# SmartLightsMini.net
KiCad netlist of a schematic drawn in EasyEDA
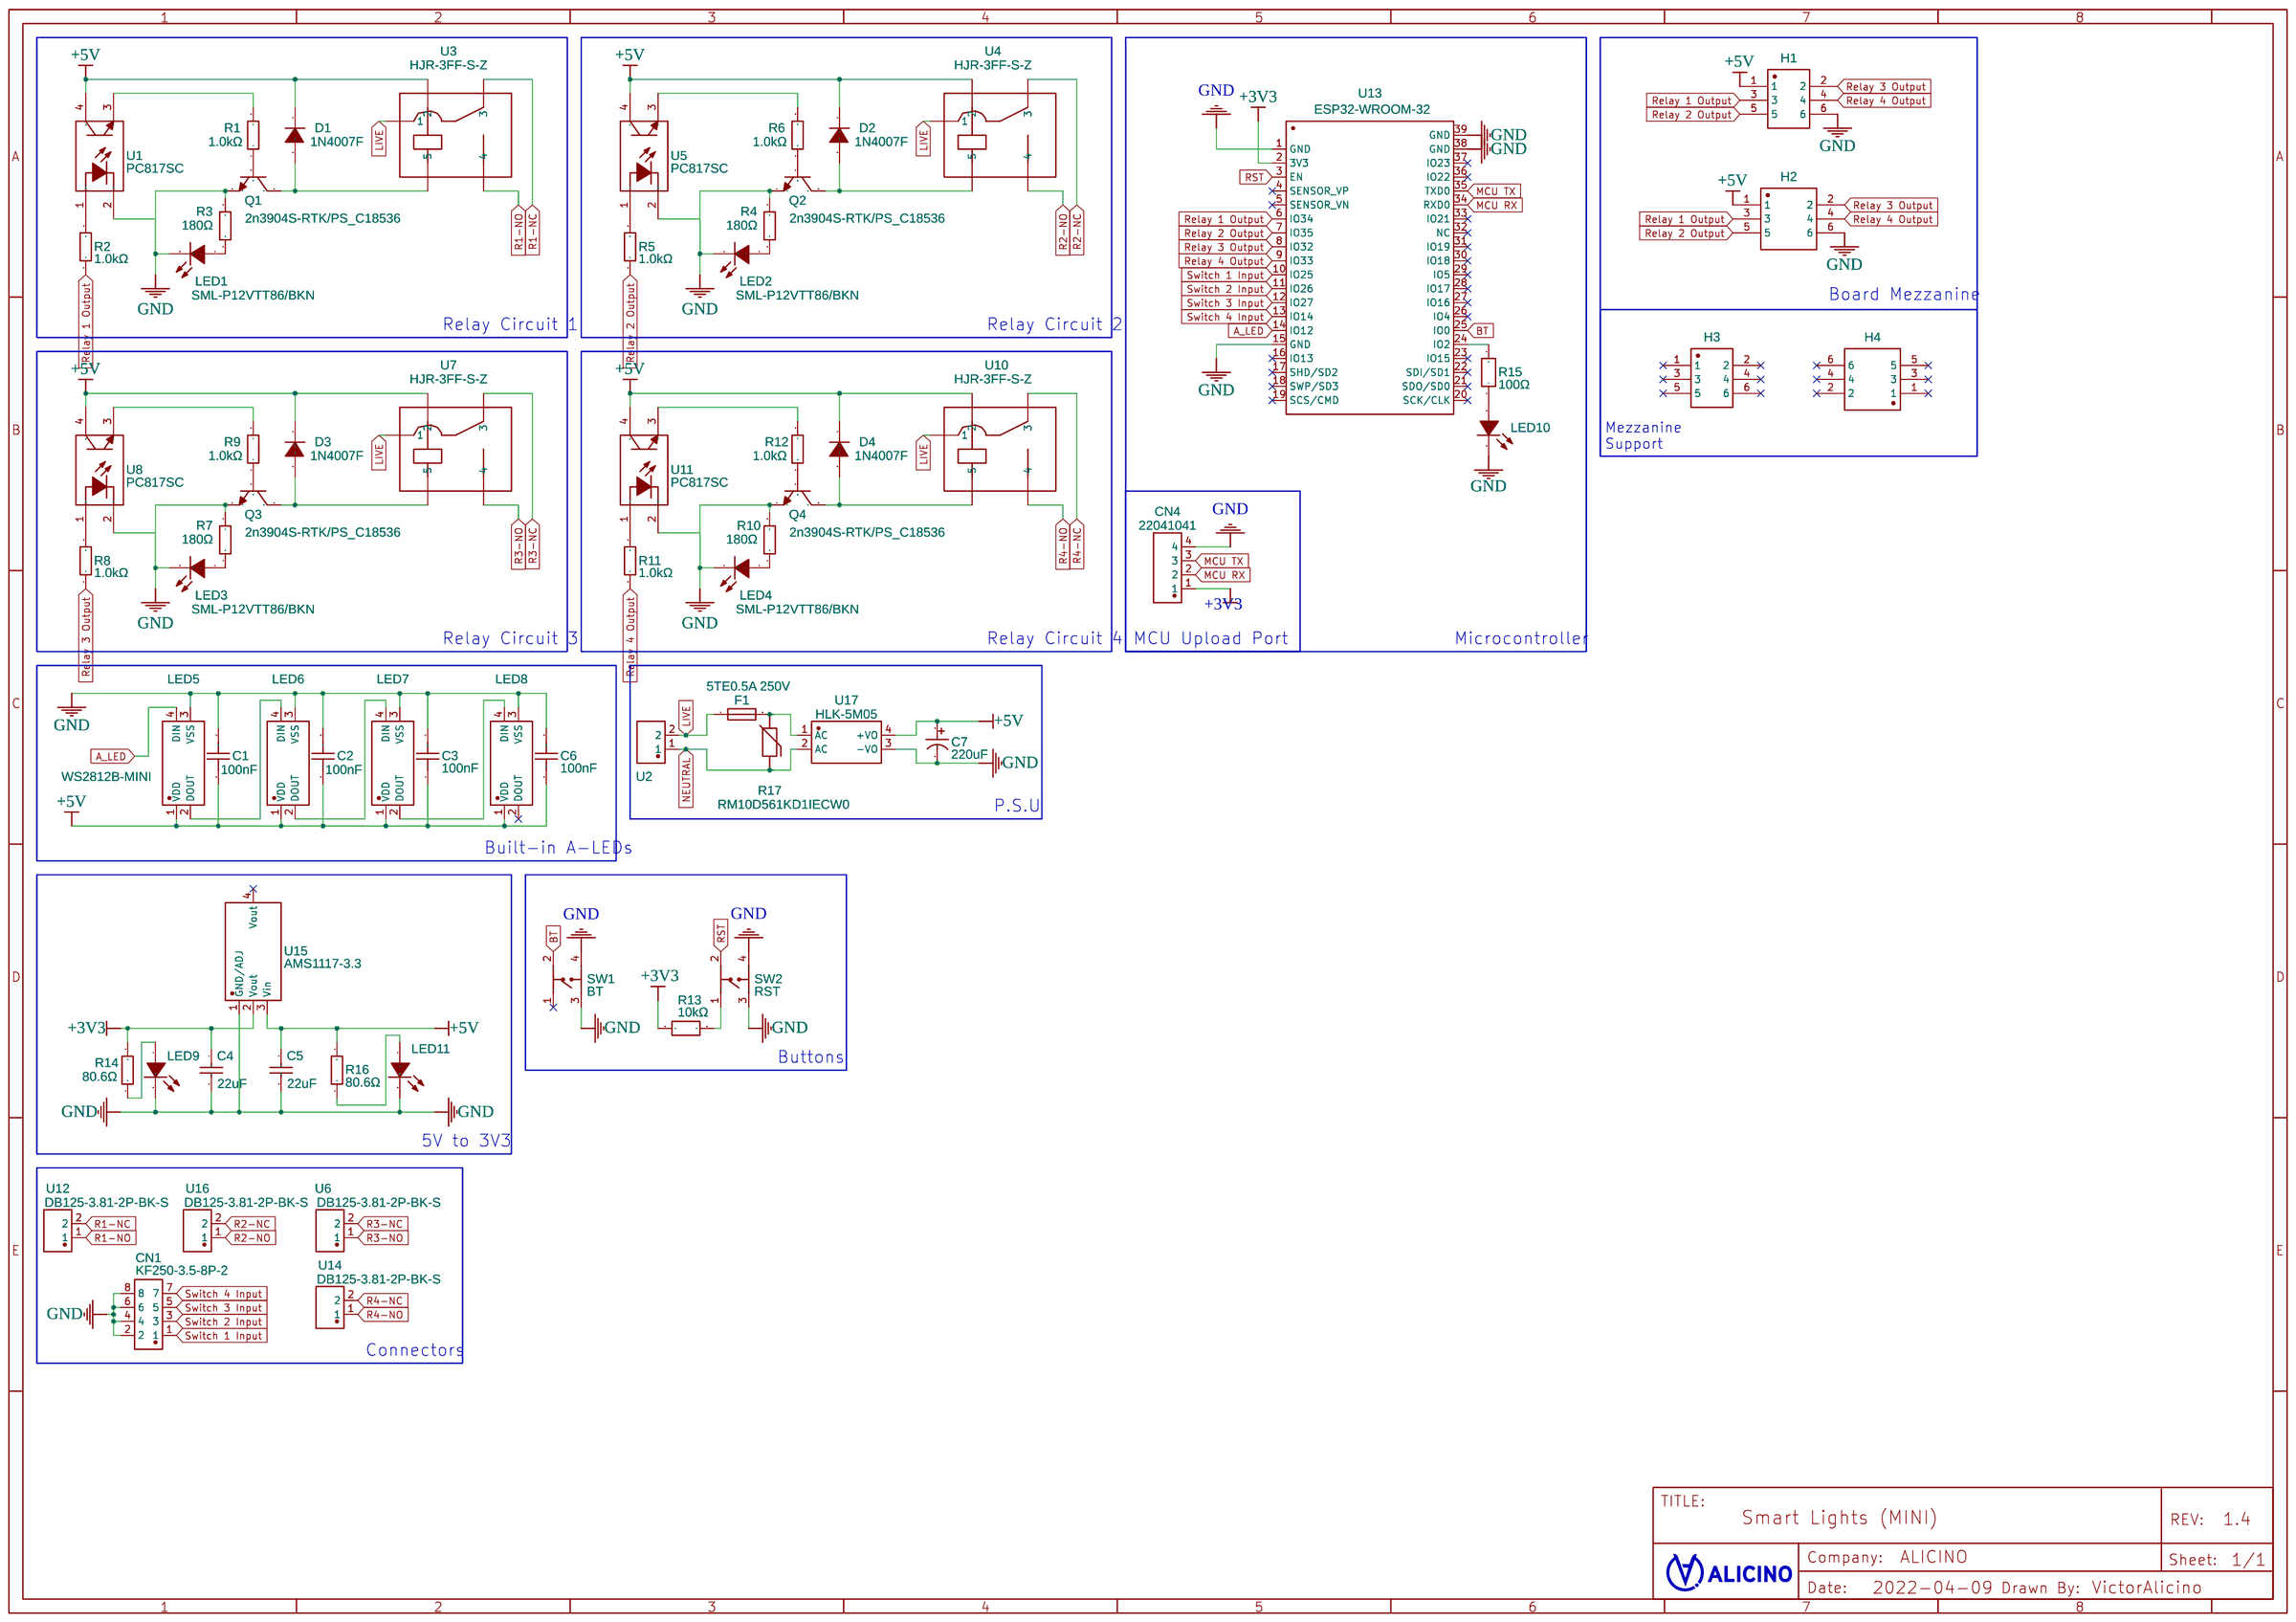
[diagram p0: schematic sheet]

(export (version "E")
  (design (tool "Eeschema 10.0.6"))
  (components
    (comp (ref "C1")
      (value "100nF")
      (fields
        (field (name "BOM_Manufacturer Part") "06035C104KAZ2A")
        (field (name "BOM_Supplier Part") "C212614")
      )
      (libsource (lib "") (part "06035C104KAZ2A"))
    )
    (comp (ref "C2")
      (value "100nF")
      (fields
        (field (name "BOM_Manufacturer Part") "06035C104KAZ2A")
        (field (name "BOM_Supplier Part") "C212614")
      )
      (libsource (lib "") (part "06035C104KAZ2A"))
    )
    (comp (ref "C3")
      (value "100nF")
      (fields
        (field (name "BOM_Manufacturer Part") "06035C104KAZ2A")
        (field (name "BOM_Supplier Part") "C212614")
      )
      (libsource (lib "") (part "06035C104KAZ2A"))
    )
    (comp (ref "C4")
      (value "22uF")
      (fields
        (field (name "BOM_Manufacturer Part") "06036D226MAT2A")
        (field (name "BOM_Supplier Part") "C140720")
      )
      (libsource (lib "") (part "06036D226MAT2A_1"))
    )
    (comp (ref "C5")
      (value "22uF")
      (fields
        (field (name "BOM_Manufacturer Part") "06036D226MAT2A")
        (field (name "BOM_Supplier Part") "C140720")
      )
      (libsource (lib "") (part "06036D226MAT2A"))
    )
    (comp (ref "C6")
      (value "100nF")
      (fields
        (field (name "BOM_Manufacturer Part") "06035C104KAZ2A")
        (field (name "BOM_Supplier Part") "C212614")
      )
      (libsource (lib "") (part "06035C104KAZ2A"))
    )
    (comp (ref "C7")
      (value "220uF")
      (fields
        (field (name "BOM_Manufacturer Part") "EEEHA1C221AP")
        (field (name "BOM_Supplier Part") "C336793")
      )
      (libsource (lib "") (part "EEEHA1C221AP"))
    )
    (comp (ref "CN1")
      (value "KF250-3.5-8P-2")
      (fields (field (name "BOM_Supplier Part") "C475169"))
      (libsource (lib "") (part "KF250-3.5-8P-2"))
    )
    (comp (ref "CN4")
      (value "22041041")
      (fields (field (name "BOM_Supplier Part") "C185196"))
      (libsource (lib "") (part "22041041"))
    )
    (comp (ref "D1")
      (value "1N4007F")
      (fields (field (name "BOM_Supplier Part") "C110856"))
      (libsource (lib "") (part "1N4007F"))
    )
    (comp (ref "D2")
      (value "1N4007F")
      (fields (field (name "BOM_Supplier Part") "C110856"))
      (libsource (lib "") (part "1N4007F"))
    )
    (comp (ref "D3")
      (value "1N4007F")
      (fields (field (name "BOM_Supplier Part") "C110856"))
      (libsource (lib "") (part "1N4007F"))
    )
    (comp (ref "D4")
      (value "1N4007F")
      (fields (field (name "BOM_Supplier Part") "C110856"))
      (libsource (lib "") (part "1N4007F"))
    )
    (comp (ref "F1")
      (value "5TE0.5A 250V")
      (fields (field (name "BOM_Supplier Part") "C140483"))
      (libsource (lib "") (part "5TE0.5A 250V"))
    )
    (comp (ref "H1")
      (value "210SMT-2*3P Gold-plated black")
      (fields (field (name "BOM_Supplier Part") "C124390"))
      (libsource (lib "") (part "210SMT-2*3P Gold-plated black"))
    )
    (comp (ref "H2")
      (value "220S-2*3P H=8.5MM Ytype Gold-plated")
      (fields (field (name "BOM_Supplier Part") "C124421"))
      (libsource (lib "") (part "220S-2*3P H=8.5MM Ytype Gold-plated"))
    )
    (comp (ref "H3")
      (value "210SMT-2*3P Gold-plated black")
      (fields (field (name "BOM_Supplier Part") "C124390"))
      (libsource (lib "") (part "210SMT-2*3P Gold-plated black"))
    )
    (comp (ref "H4")
      (value "220S-2*3P H=8.5MM Ytype Gold-plated")
      (fields (field (name "BOM_Supplier Part") "C124421"))
      (libsource (lib "") (part "220S-2*3P H=8.5MM Ytype Gold-plated_1"))
    )
    (comp (ref "LED1")
      (value "SML-P12VTT86/BKN")
      (fields (field (name "BOM_Supplier Part") "C184649"))
      (libsource (lib "") (part "SML-P12VTT86/BKN"))
    )
    (comp (ref "LED2")
      (value "SML-P12VTT86/BKN")
      (fields (field (name "BOM_Supplier Part") "C184649"))
      (libsource (lib "") (part "SML-P12VTT86/BKN"))
    )
    (comp (ref "LED3")
      (value "SML-P12VTT86/BKN")
      (fields (field (name "BOM_Supplier Part") "C184649"))
      (libsource (lib "") (part "SML-P12VTT86/BKN"))
    )
    (comp (ref "LED4")
      (value "SML-P12VTT86/BKN")
      (fields (field (name "BOM_Supplier Part") "C184649"))
      (libsource (lib "") (part "SML-P12VTT86/BKN"))
    )
    (comp (ref "LED5")
      (value "WS2812B-MINI")
      (fields
        (field (name "BOM_Manufacturer Part") "WS2812B-Mini")
        (field (name "BOM_Supplier Part") "C527089")
      )
      (libsource (lib "") (part "WS2812B-MINI"))
    )
    (comp (ref "LED6")
      (value "WS2812B-MINI")
      (fields
        (field (name "BOM_Manufacturer Part") "WS2812B-Mini")
        (field (name "BOM_Supplier Part") "C527089")
      )
      (libsource (lib "") (part "WS2812B-MINI"))
    )
    (comp (ref "LED7")
      (value "WS2812B-MINI")
      (fields
        (field (name "BOM_Manufacturer Part") "WS2812B-Mini")
        (field (name "BOM_Supplier Part") "C527089")
      )
      (libsource (lib "") (part "WS2812B-MINI"))
    )
    (comp (ref "LED8")
      (value "WS2812B-MINI")
      (fields
        (field (name "BOM_Manufacturer Part") "WS2812B-Mini")
        (field (name "BOM_Supplier Part") "C527089")
      )
      (libsource (lib "") (part "WS2812B-MINI"))
    )
    (comp (ref "LED9")
      (value "SML-P12VTT86/BKN")
      (fields (field (name "BOM_Supplier Part") "C184649"))
      (libsource (lib "") (part "SML-P12VTT86/BKN_1"))
    )
    (comp (ref "LED10")
      (value "19-21UYC/S530-A2/TR8")
      (fields (field (name "BOM_Supplier Part") "C90109"))
      (libsource (lib "") (part "19-21UYC/S530-A2/TR8"))
    )
    (comp (ref "LED11")
      (value "SML-P12VTT86/BKN")
      (fields (field (name "BOM_Supplier Part") "C184649"))
      (libsource (lib "") (part "SML-P12VTT86/BKN_1"))
    )
    (comp (ref "Q1")
      (value "2n3904S-RTK/PS_C18536")
      (fields
        (field (name "BOM_Manufacturer Part") "2n3904S-RTK/PS")
        (field (name "BOM_Supplier Part") "C18536")
      )
      (libsource (lib "") (part "2n3904S-RTK/PS_C18536"))
    )
    (comp (ref "Q2")
      (value "2n3904S-RTK/PS_C18536")
      (fields
        (field (name "BOM_Manufacturer Part") "2n3904S-RTK/PS")
        (field (name "BOM_Supplier Part") "C18536")
      )
      (libsource (lib "") (part "2n3904S-RTK/PS_C18536"))
    )
    (comp (ref "Q3")
      (value "2n3904S-RTK/PS_C18536")
      (fields
        (field (name "BOM_Manufacturer Part") "2n3904S-RTK/PS")
        (field (name "BOM_Supplier Part") "C18536")
      )
      (libsource (lib "") (part "2n3904S-RTK/PS_C18536"))
    )
    (comp (ref "Q4")
      (value "2n3904S-RTK/PS_C18536")
      (fields
        (field (name "BOM_Manufacturer Part") "2n3904S-RTK/PS")
        (field (name "BOM_Supplier Part") "C18536")
      )
      (libsource (lib "") (part "2n3904S-RTK/PS_C18536"))
    )
    (comp (ref "R1")
      (value "1.0kΩ")
      (fields
        (field (name "BOM_Manufacturer Part") "AECR0603F1K00K9")
        (field (name "BOM_Supplier Part") "C328340")
      )
      (libsource (lib "") (part "AECR0603F1K00K9"))
    )
    (comp (ref "R2")
      (value "1.0kΩ")
      (fields
        (field (name "BOM_Manufacturer Part") "AECR0603F1K00K9")
        (field (name "BOM_Supplier Part") "C328340")
      )
      (libsource (lib "") (part "AECR0603F1K00K9"))
    )
    (comp (ref "R3")
      (value "180Ω")
      (fields
        (field (name "BOM_Manufacturer Part") "AECR0603F180RK9")
        (field (name "BOM_Supplier Part") "C352360")
      )
      (libsource (lib "") (part "AECR0603F180RK9"))
    )
    (comp (ref "R4")
      (value "180Ω")
      (fields
        (field (name "BOM_Manufacturer Part") "AECR0603F180RK9")
        (field (name "BOM_Supplier Part") "C352360")
      )
      (libsource (lib "") (part "AECR0603F180RK9"))
    )
    (comp (ref "R5")
      (value "1.0kΩ")
      (fields
        (field (name "BOM_Manufacturer Part") "AECR0603F1K00K9")
        (field (name "BOM_Supplier Part") "C328340")
      )
      (libsource (lib "") (part "AECR0603F1K00K9"))
    )
    (comp (ref "R6")
      (value "1.0kΩ")
      (fields
        (field (name "BOM_Manufacturer Part") "AECR0603F1K00K9")
        (field (name "BOM_Supplier Part") "C328340")
      )
      (libsource (lib "") (part "AECR0603F1K00K9"))
    )
    (comp (ref "R7")
      (value "180Ω")
      (fields
        (field (name "BOM_Manufacturer Part") "AECR0603F180RK9")
        (field (name "BOM_Supplier Part") "C352360")
      )
      (libsource (lib "") (part "AECR0603F180RK9"))
    )
    (comp (ref "R8")
      (value "1.0kΩ")
      (fields
        (field (name "BOM_Manufacturer Part") "AECR0603F1K00K9")
        (field (name "BOM_Supplier Part") "C328340")
      )
      (libsource (lib "") (part "AECR0603F1K00K9"))
    )
    (comp (ref "R9")
      (value "1.0kΩ")
      (fields
        (field (name "BOM_Manufacturer Part") "AECR0603F1K00K9")
        (field (name "BOM_Supplier Part") "C328340")
      )
      (libsource (lib "") (part "AECR0603F1K00K9"))
    )
    (comp (ref "R10")
      (value "180Ω")
      (fields
        (field (name "BOM_Manufacturer Part") "AECR0603F180RK9")
        (field (name "BOM_Supplier Part") "C352360")
      )
      (libsource (lib "") (part "AECR0603F180RK9"))
    )
    (comp (ref "R11")
      (value "1.0kΩ")
      (fields
        (field (name "BOM_Manufacturer Part") "AECR0603F1K00K9")
        (field (name "BOM_Supplier Part") "C328340")
      )
      (libsource (lib "") (part "AECR0603F1K00K9"))
    )
    (comp (ref "R12")
      (value "1.0kΩ")
      (fields
        (field (name "BOM_Manufacturer Part") "AECR0603F1K00K9")
        (field (name "BOM_Supplier Part") "C328340")
      )
      (libsource (lib "") (part "AECR0603F1K00K9"))
    )
    (comp (ref "R13")
      (value "10kΩ")
      (fields
        (field (name "BOM_Manufacturer Part") "PTFR0603D10K0P9")
        (field (name "BOM_Supplier Part") "C375971")
      )
      (libsource (lib "") (part "PTFR0603D10K0P9"))
    )
    (comp (ref "R14")
      (value "80.6Ω")
      (fields
        (field (name "BOM_Manufacturer Part") "HPCR0603F80R6K9")
        (field (name "BOM_Supplier Part") "C365216")
      )
      (libsource (lib "") (part "HPCR0603F80R6K9"))
    )
    (comp (ref "R15")
      (value "100Ω")
      (fields
        (field (name "BOM_Manufacturer Part") "PTFR0603B100RN9")
        (field (name "BOM_Supplier Part") "C394538")
      )
      (libsource (lib "") (part "PTFR0603B100RN9"))
    )
    (comp (ref "R16")
      (value "80.6Ω")
      (fields
        (field (name "BOM_Manufacturer Part") "HPCR0603F80R6K9")
        (field (name "BOM_Supplier Part") "C365216")
      )
      (libsource (lib "") (part "HPCR0603F80R6K9"))
    )
    (comp (ref "R17")
      (value "RM10D561KD1IECW0")
      (fields (field (name "BOM_Supplier Part") "C253970"))
      (libsource (lib "") (part "RM10D561KD1IECW0"))
    )
    (comp (ref "SW1")
      (value "BT")
      (fields
        (field (name "BOM_Manufacturer Part") "TSD003A04526A02")
        (field (name "BOM_Supplier Part") "C2888576")
      )
      (libsource (lib "") (part "TSD003A04526A02"))
    )
    (comp (ref "SW2")
      (value "RST")
      (fields
        (field (name "BOM_Manufacturer Part") "TSD003A04526A02")
        (field (name "BOM_Supplier Part") "C2888576")
      )
      (libsource (lib "") (part "TSD003A04526A02"))
    )
    (comp (ref "U1")
      (value "PC817SC")
      (fields (field (name "BOM_Supplier Part") "C115502"))
      (libsource (lib "") (part "PC817SC"))
    )
    (comp (ref "U2")
      (value "DB125-3.81-2P-RD")
      (fields (field (name "BOM_Supplier Part") "C881703"))
      (libsource (lib "") (part "DB125-3.81-2P-RD"))
    )
    (comp (ref "U3")
      (value "HJR-3FF-S-Z")
      (fields (field (name "BOM_Manufacturer Part") "1366512"))
      (libsource (lib "") (part "HJR-3FF-S-Z"))
    )
    (comp (ref "U4")
      (value "HJR-3FF-S-Z")
      (fields (field (name "BOM_Manufacturer Part") "1366512"))
      (libsource (lib "") (part "HJR-3FF-S-Z"))
    )
    (comp (ref "U5")
      (value "PC817SC")
      (fields (field (name "BOM_Supplier Part") "C115502"))
      (libsource (lib "") (part "PC817SC"))
    )
    (comp (ref "U6")
      (value "DB125-3.81-2P-BK-S")
      (fields (field (name "BOM_Supplier Part") "C430618"))
      (libsource (lib "") (part "DB125-3.81-2P-BK-S"))
    )
    (comp (ref "U7")
      (value "HJR-3FF-S-Z")
      (fields (field (name "BOM_Manufacturer Part") "1366512"))
      (libsource (lib "") (part "HJR-3FF-S-Z"))
    )
    (comp (ref "U8")
      (value "PC817SC")
      (fields (field (name "BOM_Supplier Part") "C115502"))
      (libsource (lib "") (part "PC817SC"))
    )
    (comp (ref "U10")
      (value "HJR-3FF-S-Z")
      (fields (field (name "BOM_Manufacturer Part") "1366512"))
      (libsource (lib "") (part "HJR-3FF-S-Z"))
    )
    (comp (ref "U11")
      (value "PC817SC")
      (fields (field (name "BOM_Supplier Part") "C115502"))
      (libsource (lib "") (part "PC817SC"))
    )
    (comp (ref "U12")
      (value "DB125-3.81-2P-BK-S")
      (fields (field (name "BOM_Supplier Part") "C430618"))
      (libsource (lib "") (part "DB125-3.81-2P-BK-S"))
    )
    (comp (ref "U13")
      (value "ESP32-WROOM-32")
      (fields (field (name "BOM_Supplier Part") "C82899"))
      (libsource (lib "") (part "ESP32-WROOM-32"))
    )
    (comp (ref "U14")
      (value "DB125-3.81-2P-BK-S")
      (fields (field (name "BOM_Supplier Part") "C430618"))
      (libsource (lib "") (part "DB125-3.81-2P-BK-S"))
    )
    (comp (ref "U15")
      (value "AMS1117-3.3")
      (fields (field (name "BOM_Supplier Part") "C6186"))
      (libsource (lib "") (part "AMS1117-3.3"))
    )
    (comp (ref "U16")
      (value "DB125-3.81-2P-BK-S")
      (fields (field (name "BOM_Supplier Part") "C430618"))
      (libsource (lib "") (part "DB125-3.81-2P-BK-S"))
    )
    (comp (ref "U17")
      (value "HLK-5M05")
      (fields (field (name "BOM_Supplier Part") "C209907"))
      (libsource (lib "") (part "HLK-5M05"))
    )
  )
  (nets
    (net (code "1") (name "+3V3") (class "Default")
      (node (ref "C4") (pin "1") (pinfunction "1_1") (pintype "input"))
      (node (ref "CN4") (pin "1") (pinfunction "1_1") (pintype "unspecified"))
      (node (ref "R13") (pin "1") (pinfunction "1_1") (pintype "unspecified"))
      (node (ref "R14") (pin "2") (pinfunction "2_2") (pintype "unspecified"))
      (node (ref "U13") (pin "2") (pinfunction "3V3_2") (pintype "unspecified"))
      (node (ref "U15") (pin "2") (pinfunction "Vout_2") (pintype "unspecified"))
    )
    (net (code "2") (name "+5V") (class "Default")
      (node (ref "C1") (pin "1") (pinfunction "1_1") (pintype "unspecified"))
      (node (ref "C2") (pin "1") (pinfunction "1_1") (pintype "unspecified"))
      (node (ref "C3") (pin "1") (pinfunction "1_1") (pintype "unspecified"))
      (node (ref "C5") (pin "2") (pinfunction "2_2") (pintype "input"))
      (node (ref "C6") (pin "1") (pinfunction "1_1") (pintype "unspecified"))
      (node (ref "C7") (pin "1") (pinfunction "1_1") (pintype "input"))
      (node (ref "D1") (pin "1") (pinfunction "C_1") (pintype "unspecified"))
      (node (ref "D2") (pin "1") (pinfunction "C_1") (pintype "unspecified"))
      (node (ref "D3") (pin "1") (pinfunction "C_1") (pintype "unspecified"))
      (node (ref "D4") (pin "1") (pinfunction "C_1") (pintype "unspecified"))
      (node (ref "H1") (pin "1") (pinfunction "1_1") (pintype "unspecified"))
      (node (ref "H2") (pin "1") (pinfunction "1_1") (pintype "unspecified"))
      (node (ref "LED5") (pin "1") (pinfunction "VDD_1") (pintype "unspecified"))
      (node (ref "LED6") (pin "1") (pinfunction "VDD_1") (pintype "unspecified"))
      (node (ref "LED7") (pin "1") (pinfunction "VDD_1") (pintype "unspecified"))
      (node (ref "LED8") (pin "1") (pinfunction "VDD_1") (pintype "unspecified"))
      (node (ref "R16") (pin "2") (pinfunction "2_2") (pintype "unspecified"))
      (node (ref "U1") (pin "4") (pinfunction "COL_4") (pintype "unspecified"))
      (node (ref "U10") (pin "2") (pinfunction "2_2") (pintype "unspecified"))
      (node (ref "U11") (pin "4") (pinfunction "COL_4") (pintype "unspecified"))
      (node (ref "U15") (pin "3") (pinfunction "Vin_3") (pintype "unspecified"))
      (node (ref "U17") (pin "4") (pinfunction "+VO_4") (pintype "unspecified"))
      (node (ref "U3") (pin "2") (pinfunction "2_2") (pintype "unspecified"))
      (node (ref "U4") (pin "2") (pinfunction "2_2") (pintype "unspecified"))
      (node (ref "U5") (pin "4") (pinfunction "COL_4") (pintype "unspecified"))
      (node (ref "U7") (pin "2") (pinfunction "2_2") (pintype "unspecified"))
      (node (ref "U8") (pin "4") (pinfunction "COL_4") (pintype "unspecified"))
    )
    (net (code "3") (name "A_LED") (class "Default")
      (node (ref "LED5") (pin "4") (pinfunction "DIN_4") (pintype "unspecified"))
      (node (ref "U13") (pin "14") (pinfunction "IO12_14") (pintype "unspecified"))
    )
    (net (code "4") (name "BT") (class "Default")
      (node (ref "SW1") (pin "2") (pinfunction "2_2") (pintype "unspecified"))
      (node (ref "U13") (pin "25") (pinfunction "IO0_25") (pintype "unspecified"))
    )
    (net (code "5") (name "GND") (class "Default")
      (node (ref "C1") (pin "2") (pinfunction "2_2") (pintype "unspecified"))
      (node (ref "C2") (pin "2") (pinfunction "2_2") (pintype "unspecified"))
      (node (ref "C3") (pin "2") (pinfunction "2_2") (pintype "unspecified"))
      (node (ref "C4") (pin "2") (pinfunction "2_2") (pintype "input"))
      (node (ref "C5") (pin "1") (pinfunction "1_1") (pintype "input"))
      (node (ref "C6") (pin "2") (pinfunction "2_2") (pintype "unspecified"))
      (node (ref "C7") (pin "2") (pinfunction "2_2") (pintype "input"))
      (node (ref "CN1") (pin "2") (pinfunction "2_2") (pintype "unspecified"))
      (node (ref "CN1") (pin "4") (pinfunction "4_4") (pintype "unspecified"))
      (node (ref "CN1") (pin "6") (pinfunction "6_6") (pintype "unspecified"))
      (node (ref "CN1") (pin "8") (pinfunction "8_8") (pintype "unspecified"))
      (node (ref "CN4") (pin "4") (pinfunction "4_4") (pintype "unspecified"))
      (node (ref "H1") (pin "6") (pinfunction "6_6") (pintype "unspecified"))
      (node (ref "H2") (pin "6") (pinfunction "6_6") (pintype "unspecified"))
      (node (ref "LED1") (pin "2") (pinfunction "C_2") (pintype "unspecified"))
      (node (ref "LED10") (pin "2") (pinfunction "K_2") (pintype "unspecified"))
      (node (ref "LED11") (pin "2") (pinfunction "C_2") (pintype "unspecified"))
      (node (ref "LED2") (pin "2") (pinfunction "C_2") (pintype "unspecified"))
      (node (ref "LED3") (pin "2") (pinfunction "C_2") (pintype "unspecified"))
      (node (ref "LED4") (pin "2") (pinfunction "C_2") (pintype "unspecified"))
      (node (ref "LED5") (pin "3") (pinfunction "VSS_3") (pintype "unspecified"))
      (node (ref "LED6") (pin "3") (pinfunction "VSS_3") (pintype "unspecified"))
      (node (ref "LED7") (pin "3") (pinfunction "VSS_3") (pintype "unspecified"))
      (node (ref "LED8") (pin "3") (pinfunction "VSS_3") (pintype "unspecified"))
      (node (ref "LED9") (pin "2") (pinfunction "C_2") (pintype "unspecified"))
      (node (ref "Q1") (pin "1") (pinfunction "E_1") (pintype "input"))
      (node (ref "Q2") (pin "1") (pinfunction "E_1") (pintype "input"))
      (node (ref "Q3") (pin "1") (pinfunction "E_1") (pintype "input"))
      (node (ref "Q4") (pin "1") (pinfunction "E_1") (pintype "input"))
      (node (ref "R10") (pin "2") (pinfunction "2_2") (pintype "unspecified"))
      (node (ref "R3") (pin "2") (pinfunction "2_2") (pintype "unspecified"))
      (node (ref "R4") (pin "2") (pinfunction "2_2") (pintype "unspecified"))
      (node (ref "R7") (pin "2") (pinfunction "2_2") (pintype "unspecified"))
      (node (ref "SW1") (pin "3") (pinfunction "3_3") (pintype "unspecified"))
      (node (ref "SW1") (pin "4") (pinfunction "4_4") (pintype "unspecified"))
      (node (ref "SW2") (pin "3") (pinfunction "3_3") (pintype "unspecified"))
      (node (ref "SW2") (pin "4") (pinfunction "4_4") (pintype "unspecified"))
      (node (ref "U1") (pin "2") (pinfunction "CAT_2") (pintype "unspecified"))
      (node (ref "U11") (pin "2") (pinfunction "CAT_2") (pintype "unspecified"))
      (node (ref "U13") (pin "1") (pinfunction "GND_1") (pintype "unspecified"))
      (node (ref "U13") (pin "15") (pinfunction "GND_15") (pintype "unspecified"))
      (node (ref "U13") (pin "38") (pinfunction "GND_38") (pintype "unspecified"))
      (node (ref "U13") (pin "39") (pinfunction "GND_39") (pintype "unspecified"))
      (node (ref "U15") (pin "1") (pinfunction "GND/ADJ_1") (pintype "unspecified"))
      (node (ref "U17") (pin "3") (pinfunction "-VO_3") (pintype "unspecified"))
      (node (ref "U5") (pin "2") (pinfunction "CAT_2") (pintype "unspecified"))
      (node (ref "U8") (pin "2") (pinfunction "CAT_2") (pintype "unspecified"))
    )
    (net (code "6") (name "LIVE") (class "Default")
      (node (ref "F1") (pin "1") (pinfunction "1_1") (pintype "unspecified"))
      (node (ref "U10") (pin "1") (pinfunction "1_1") (pintype "unspecified"))
      (node (ref "U2") (pin "2") (pinfunction "2_2") (pintype "unspecified"))
      (node (ref "U3") (pin "1") (pinfunction "1_1") (pintype "unspecified"))
      (node (ref "U4") (pin "1") (pinfunction "1_1") (pintype "unspecified"))
      (node (ref "U7") (pin "1") (pinfunction "1_1") (pintype "unspecified"))
    )
    (net (code "7") (name "MCU RX") (class "Default")
      (node (ref "CN4") (pin "2") (pinfunction "2_2") (pintype "unspecified"))
      (node (ref "U13") (pin "34") (pinfunction "RXD0_34") (pintype "unspecified"))
    )
    (net (code "8") (name "MCU TX") (class "Default")
      (node (ref "CN4") (pin "3") (pinfunction "3_3") (pintype "unspecified"))
      (node (ref "U13") (pin "35") (pinfunction "TXD0_35") (pintype "unspecified"))
    )
    (net (code "9") (name "NEUTRAL") (class "Default")
      (node (ref "R17") (pin "1") (pinfunction "1_1") (pintype "unspecified"))
      (node (ref "U17") (pin "2") (pinfunction "AC_2") (pintype "unspecified"))
      (node (ref "U2") (pin "1") (pinfunction "1_1") (pintype "unspecified"))
    )
    (net (code "10") (name "Net-(D1-A)") (class "Default")
      (node (ref "D1") (pin "2") (pinfunction "A_2") (pintype "unspecified"))
      (node (ref "Q1") (pin "3") (pinfunction "C_3") (pintype "input"))
      (node (ref "U3") (pin "5") (pinfunction "5_5") (pintype "unspecified"))
    )
    (net (code "11") (name "Net-(D2-A)") (class "Default")
      (node (ref "D2") (pin "2") (pinfunction "A_2") (pintype "unspecified"))
      (node (ref "Q2") (pin "3") (pinfunction "C_3") (pintype "input"))
      (node (ref "U4") (pin "5") (pinfunction "5_5") (pintype "unspecified"))
    )
    (net (code "12") (name "Net-(D3-A)") (class "Default")
      (node (ref "D3") (pin "2") (pinfunction "A_2") (pintype "unspecified"))
      (node (ref "Q3") (pin "3") (pinfunction "C_3") (pintype "input"))
      (node (ref "U7") (pin "5") (pinfunction "5_5") (pintype "unspecified"))
    )
    (net (code "13") (name "Net-(D4-A)") (class "Default")
      (node (ref "D4") (pin "2") (pinfunction "A_2") (pintype "unspecified"))
      (node (ref "Q4") (pin "3") (pinfunction "C_3") (pintype "input"))
      (node (ref "U10") (pin "5") (pinfunction "5_5") (pintype "unspecified"))
    )
    (net (code "14") (name "Net-(F1-Pad2)") (class "Default")
      (node (ref "F1") (pin "2") (pinfunction "2_2") (pintype "unspecified"))
      (node (ref "R17") (pin "2") (pinfunction "2_2") (pintype "unspecified"))
      (node (ref "U17") (pin "1") (pinfunction "AC_1") (pintype "unspecified"))
    )
    (net (code "15") (name "Net-(LED1-A)") (class "Default")
      (node (ref "LED1") (pin "1") (pinfunction "A_1") (pintype "unspecified"))
      (node (ref "R3") (pin "1") (pinfunction "1_1") (pintype "unspecified"))
    )
    (net (code "16") (name "Net-(LED2-A)") (class "Default")
      (node (ref "LED2") (pin "1") (pinfunction "A_1") (pintype "unspecified"))
      (node (ref "R4") (pin "1") (pinfunction "1_1") (pintype "unspecified"))
    )
    (net (code "17") (name "Net-(LED3-A)") (class "Default")
      (node (ref "LED3") (pin "1") (pinfunction "A_1") (pintype "unspecified"))
      (node (ref "R7") (pin "1") (pinfunction "1_1") (pintype "unspecified"))
    )
    (net (code "18") (name "Net-(LED4-A)") (class "Default")
      (node (ref "LED4") (pin "1") (pinfunction "A_1") (pintype "unspecified"))
      (node (ref "R10") (pin "1") (pinfunction "1_1") (pintype "unspecified"))
    )
    (net (code "19") (name "Net-(LED5-DOUT)") (class "Default")
      (node (ref "LED5") (pin "2") (pinfunction "DOUT_2") (pintype "unspecified"))
      (node (ref "LED6") (pin "4") (pinfunction "DIN_4") (pintype "unspecified"))
    )
    (net (code "20") (name "Net-(LED6-DOUT)") (class "Default")
      (node (ref "LED6") (pin "2") (pinfunction "DOUT_2") (pintype "unspecified"))
      (node (ref "LED7") (pin "4") (pinfunction "DIN_4") (pintype "unspecified"))
    )
    (net (code "21") (name "Net-(LED7-DOUT)") (class "Default")
      (node (ref "LED7") (pin "2") (pinfunction "DOUT_2") (pintype "unspecified"))
      (node (ref "LED8") (pin "4") (pinfunction "DIN_4") (pintype "unspecified"))
    )
    (net (code "22") (name "Net-(LED9-A)") (class "Default")
      (node (ref "LED9") (pin "1") (pinfunction "A_1") (pintype "unspecified"))
      (node (ref "R14") (pin "1") (pinfunction "1_1") (pintype "unspecified"))
    )
    (net (code "23") (name "Net-(LED10-A)") (class "Default")
      (node (ref "LED10") (pin "1") (pinfunction "A_1") (pintype "unspecified"))
      (node (ref "R15") (pin "1") (pinfunction "1_1") (pintype "unspecified"))
    )
    (net (code "24") (name "Net-(LED11-A)") (class "Default")
      (node (ref "LED11") (pin "1") (pinfunction "A_1") (pintype "unspecified"))
      (node (ref "R16") (pin "1") (pinfunction "1_1") (pintype "unspecified"))
    )
    (net (code "25") (name "Net-(Q1-B)") (class "Default")
      (node (ref "Q1") (pin "2") (pinfunction "B_2") (pintype "input"))
      (node (ref "R1") (pin "1") (pinfunction "1_1") (pintype "unspecified"))
    )
    (net (code "26") (name "Net-(Q2-B)") (class "Default")
      (node (ref "Q2") (pin "2") (pinfunction "B_2") (pintype "input"))
      (node (ref "R6") (pin "1") (pinfunction "1_1") (pintype "unspecified"))
    )
    (net (code "27") (name "Net-(Q3-B)") (class "Default")
      (node (ref "Q3") (pin "2") (pinfunction "B_2") (pintype "input"))
      (node (ref "R9") (pin "1") (pinfunction "1_1") (pintype "unspecified"))
    )
    (net (code "28") (name "Net-(Q4-B)") (class "Default")
      (node (ref "Q4") (pin "2") (pinfunction "B_2") (pintype "input"))
      (node (ref "R12") (pin "1") (pinfunction "1_1") (pintype "unspecified"))
    )
    (net (code "29") (name "Net-(R13-Pad2)") (class "Default")
      (node (ref "R13") (pin "2") (pinfunction "2_2") (pintype "unspecified"))
      (node (ref "SW2") (pin "1") (pinfunction "1_1") (pintype "unspecified"))
    )
    (net (code "30") (name "Net-(U1-AN)") (class "Default")
      (node (ref "R2") (pin "2") (pinfunction "2_2") (pintype "unspecified"))
      (node (ref "U1") (pin "1") (pinfunction "AN_1") (pintype "unspecified"))
    )
    (net (code "31") (name "Net-(U1-EM)") (class "Default")
      (node (ref "R1") (pin "2") (pinfunction "2_2") (pintype "unspecified"))
      (node (ref "U1") (pin "3") (pinfunction "EM_3") (pintype "unspecified"))
    )
    (net (code "32") (name "Net-(U5-AN)") (class "Default")
      (node (ref "R5") (pin "2") (pinfunction "2_2") (pintype "unspecified"))
      (node (ref "U5") (pin "1") (pinfunction "AN_1") (pintype "unspecified"))
    )
    (net (code "33") (name "Net-(U5-EM)") (class "Default")
      (node (ref "R6") (pin "2") (pinfunction "2_2") (pintype "unspecified"))
      (node (ref "U5") (pin "3") (pinfunction "EM_3") (pintype "unspecified"))
    )
    (net (code "34") (name "Net-(U8-AN)") (class "Default")
      (node (ref "R8") (pin "2") (pinfunction "2_2") (pintype "unspecified"))
      (node (ref "U8") (pin "1") (pinfunction "AN_1") (pintype "unspecified"))
    )
    (net (code "35") (name "Net-(U8-EM)") (class "Default")
      (node (ref "R9") (pin "2") (pinfunction "2_2") (pintype "unspecified"))
      (node (ref "U8") (pin "3") (pinfunction "EM_3") (pintype "unspecified"))
    )
    (net (code "36") (name "Net-(U11-AN)") (class "Default")
      (node (ref "R11") (pin "2") (pinfunction "2_2") (pintype "unspecified"))
      (node (ref "U11") (pin "1") (pinfunction "AN_1") (pintype "unspecified"))
    )
    (net (code "37") (name "Net-(U11-EM)") (class "Default")
      (node (ref "R12") (pin "2") (pinfunction "2_2") (pintype "unspecified"))
      (node (ref "U11") (pin "3") (pinfunction "EM_3") (pintype "unspecified"))
    )
    (net (code "38") (name "Net-(U13-IO2)") (class "Default")
      (node (ref "R15") (pin "2") (pinfunction "2_2") (pintype "unspecified"))
      (node (ref "U13") (pin "24") (pinfunction "IO2_24") (pintype "unspecified"))
    )
    (net (code "39") (name "R1-NC") (class "Default")
      (node (ref "U12") (pin "2") (pinfunction "2_2") (pintype "unspecified"))
      (node (ref "U3") (pin "3") (pinfunction "3_3") (pintype "unspecified"))
    )
    (net (code "40") (name "R1-NO") (class "Default")
      (node (ref "U12") (pin "1") (pinfunction "1_1") (pintype "unspecified"))
      (node (ref "U3") (pin "4") (pinfunction "4_4") (pintype "unspecified"))
    )
    (net (code "41") (name "R2-NC") (class "Default")
      (node (ref "U16") (pin "2") (pinfunction "2_2") (pintype "unspecified"))
      (node (ref "U4") (pin "3") (pinfunction "3_3") (pintype "unspecified"))
    )
    (net (code "42") (name "R2-NO") (class "Default")
      (node (ref "U16") (pin "1") (pinfunction "1_1") (pintype "unspecified"))
      (node (ref "U4") (pin "4") (pinfunction "4_4") (pintype "unspecified"))
    )
    (net (code "43") (name "R3-NC") (class "Default")
      (node (ref "U6") (pin "2") (pinfunction "2_2") (pintype "unspecified"))
      (node (ref "U7") (pin "3") (pinfunction "3_3") (pintype "unspecified"))
    )
    (net (code "44") (name "R3-NO") (class "Default")
      (node (ref "U6") (pin "1") (pinfunction "1_1") (pintype "unspecified"))
      (node (ref "U7") (pin "4") (pinfunction "4_4") (pintype "unspecified"))
    )
    (net (code "45") (name "R4-NC") (class "Default")
      (node (ref "U10") (pin "3") (pinfunction "3_3") (pintype "unspecified"))
      (node (ref "U14") (pin "2") (pinfunction "2_2") (pintype "unspecified"))
    )
    (net (code "46") (name "R4-NO") (class "Default")
      (node (ref "U10") (pin "4") (pinfunction "4_4") (pintype "unspecified"))
      (node (ref "U14") (pin "1") (pinfunction "1_1") (pintype "unspecified"))
    )
    (net (code "47") (name "RST") (class "Default")
      (node (ref "SW2") (pin "2") (pinfunction "2_2") (pintype "unspecified"))
      (node (ref "U13") (pin "3") (pinfunction "EN_3") (pintype "unspecified"))
    )
    (net (code "48") (name "Relay 1 Output") (class "Default")
      (node (ref "H1") (pin "3") (pinfunction "3_3") (pintype "unspecified"))
      (node (ref "H2") (pin "3") (pinfunction "3_3") (pintype "unspecified"))
      (node (ref "R2") (pin "1") (pinfunction "1_1") (pintype "unspecified"))
      (node (ref "U13") (pin "6") (pinfunction "IO34_6") (pintype "unspecified"))
    )
    (net (code "49") (name "Relay 2 Output") (class "Default")
      (node (ref "H1") (pin "5") (pinfunction "5_5") (pintype "unspecified"))
      (node (ref "H2") (pin "5") (pinfunction "5_5") (pintype "unspecified"))
      (node (ref "R5") (pin "1") (pinfunction "1_1") (pintype "unspecified"))
      (node (ref "U13") (pin "7") (pinfunction "IO35_7") (pintype "unspecified"))
    )
    (net (code "50") (name "Relay 3 Output") (class "Default")
      (node (ref "H1") (pin "2") (pinfunction "2_2") (pintype "unspecified"))
      (node (ref "H2") (pin "2") (pinfunction "2_2") (pintype "unspecified"))
      (node (ref "R8") (pin "1") (pinfunction "1_1") (pintype "unspecified"))
      (node (ref "U13") (pin "8") (pinfunction "IO32_8") (pintype "unspecified"))
    )
    (net (code "51") (name "Relay 4 Output") (class "Default")
      (node (ref "H1") (pin "4") (pinfunction "4_4") (pintype "unspecified"))
      (node (ref "H2") (pin "4") (pinfunction "4_4") (pintype "unspecified"))
      (node (ref "R11") (pin "1") (pinfunction "1_1") (pintype "unspecified"))
      (node (ref "U13") (pin "9") (pinfunction "IO33_9") (pintype "unspecified"))
    )
    (net (code "52") (name "Switch 1 Input") (class "Default")
      (node (ref "CN1") (pin "1") (pinfunction "1_1") (pintype "unspecified"))
      (node (ref "U13") (pin "10") (pinfunction "IO25_10") (pintype "unspecified"))
    )
    (net (code "53") (name "Switch 2 Input") (class "Default")
      (node (ref "CN1") (pin "3") (pinfunction "3_3") (pintype "unspecified"))
      (node (ref "U13") (pin "11") (pinfunction "IO26_11") (pintype "unspecified"))
    )
    (net (code "54") (name "Switch 3 Input") (class "Default")
      (node (ref "CN1") (pin "5") (pinfunction "5_5") (pintype "unspecified"))
      (node (ref "U13") (pin "12") (pinfunction "IO27_12") (pintype "unspecified"))
    )
    (net (code "55") (name "Switch 4 Input") (class "Default")
      (node (ref "CN1") (pin "7") (pinfunction "7_7") (pintype "unspecified"))
      (node (ref "U13") (pin "13") (pinfunction "IO14_13") (pintype "unspecified"))
    )
    (net (code "56") (name "unconnected-(H3-Pad1)") (class "Default")
      (node (ref "H3") (pin "1") (pinfunction "1_1") (pintype "unspecified+no_connect"))
    )
    (net (code "57") (name "unconnected-(H3-Pad2)") (class "Default")
      (node (ref "H3") (pin "2") (pinfunction "2_2") (pintype "unspecified+no_connect"))
    )
    (net (code "58") (name "unconnected-(H3-Pad3)") (class "Default")
      (node (ref "H3") (pin "3") (pinfunction "3_3") (pintype "unspecified+no_connect"))
    )
    (net (code "59") (name "unconnected-(H3-Pad4)") (class "Default")
      (node (ref "H3") (pin "4") (pinfunction "4_4") (pintype "unspecified+no_connect"))
    )
    (net (code "60") (name "unconnected-(H3-Pad5)") (class "Default")
      (node (ref "H3") (pin "5") (pinfunction "5_5") (pintype "unspecified+no_connect"))
    )
    (net (code "61") (name "unconnected-(H3-Pad6)") (class "Default")
      (node (ref "H3") (pin "6") (pinfunction "6_6") (pintype "unspecified+no_connect"))
    )
    (net (code "62") (name "unconnected-(H4-Pad1)") (class "Default")
      (node (ref "H4") (pin "1") (pinfunction "1_1") (pintype "unspecified+no_connect"))
    )
    (net (code "63") (name "unconnected-(H4-Pad2)") (class "Default")
      (node (ref "H4") (pin "2") (pinfunction "2_2") (pintype "unspecified+no_connect"))
    )
    (net (code "64") (name "unconnected-(H4-Pad3)") (class "Default")
      (node (ref "H4") (pin "3") (pinfunction "3_3") (pintype "unspecified+no_connect"))
    )
    (net (code "65") (name "unconnected-(H4-Pad4)") (class "Default")
      (node (ref "H4") (pin "4") (pinfunction "4_4") (pintype "unspecified+no_connect"))
    )
    (net (code "66") (name "unconnected-(H4-Pad5)") (class "Default")
      (node (ref "H4") (pin "5") (pinfunction "5_5") (pintype "unspecified+no_connect"))
    )
    (net (code "67") (name "unconnected-(H4-Pad6)") (class "Default")
      (node (ref "H4") (pin "6") (pinfunction "6_6") (pintype "unspecified+no_connect"))
    )
    (net (code "68") (name "unconnected-(LED8-DOUT-Pad2)") (class "Default")
      (node (ref "LED8") (pin "2") (pinfunction "DOUT_2") (pintype "unspecified+no_connect"))
    )
    (net (code "69") (name "unconnected-(SW1-Pad1)") (class "Default")
      (node (ref "SW1") (pin "1") (pinfunction "1_1") (pintype "unspecified+no_connect"))
    )
    (net (code "70") (name "unconnected-(U13-IO4-Pad26)") (class "Default")
      (node (ref "U13") (pin "26") (pinfunction "IO4_26") (pintype "unspecified+no_connect"))
    )
    (net (code "71") (name "unconnected-(U13-IO5-Pad29)") (class "Default")
      (node (ref "U13") (pin "29") (pinfunction "IO5_29") (pintype "unspecified+no_connect"))
    )
    (net (code "72") (name "unconnected-(U13-IO13-Pad16)") (class "Default")
      (node (ref "U13") (pin "16") (pinfunction "IO13_16") (pintype "unspecified+no_connect"))
    )
    (net (code "73") (name "unconnected-(U13-IO15-Pad23)") (class "Default")
      (node (ref "U13") (pin "23") (pinfunction "IO15_23") (pintype "unspecified+no_connect"))
    )
    (net (code "74") (name "unconnected-(U13-IO16-Pad27)") (class "Default")
      (node (ref "U13") (pin "27") (pinfunction "IO16_27") (pintype "unspecified+no_connect"))
    )
    (net (code "75") (name "unconnected-(U13-IO17-Pad28)") (class "Default")
      (node (ref "U13") (pin "28") (pinfunction "IO17_28") (pintype "unspecified+no_connect"))
    )
    (net (code "76") (name "unconnected-(U13-IO18-Pad30)") (class "Default")
      (node (ref "U13") (pin "30") (pinfunction "IO18_30") (pintype "unspecified+no_connect"))
    )
    (net (code "77") (name "unconnected-(U13-IO19-Pad31)") (class "Default")
      (node (ref "U13") (pin "31") (pinfunction "IO19_31") (pintype "unspecified+no_connect"))
    )
    (net (code "78") (name "unconnected-(U13-IO21-Pad33)") (class "Default")
      (node (ref "U13") (pin "33") (pinfunction "IO21_33") (pintype "unspecified+no_connect"))
    )
    (net (code "79") (name "unconnected-(U13-IO22-Pad36)") (class "Default")
      (node (ref "U13") (pin "36") (pinfunction "IO22_36") (pintype "unspecified+no_connect"))
    )
    (net (code "80") (name "unconnected-(U13-IO23-Pad37)") (class "Default")
      (node (ref "U13") (pin "37") (pinfunction "IO23_37") (pintype "unspecified+no_connect"))
    )
    (net (code "81") (name "unconnected-(U13-NC-Pad32)") (class "Default")
      (node (ref "U13") (pin "32") (pinfunction "NC_32") (pintype "unspecified+no_connect"))
    )
    (net (code "82") (name "unconnected-(U13-SCK{slash}CLK-Pad20)") (class "Default")
      (node (ref "U13") (pin "20") (pinfunction "SCK/CLK_20") (pintype "unspecified+no_connect"))
    )
    (net (code "83") (name "unconnected-(U13-SCS{slash}CMD-Pad19)") (class "Default")
      (node (ref "U13") (pin "19") (pinfunction "SCS/CMD_19") (pintype "unspecified+no_connect"))
    )
    (net (code "84") (name "unconnected-(U13-SDI{slash}SD1-Pad22)") (class "Default")
      (node (ref "U13") (pin "22") (pinfunction "SDI/SD1_22") (pintype "unspecified+no_connect"))
    )
    (net (code "85") (name "unconnected-(U13-SDO{slash}SD0-Pad21)") (class "Default")
      (node (ref "U13") (pin "21") (pinfunction "SDO/SD0_21") (pintype "unspecified+no_connect"))
    )
    (net (code "86") (name "unconnected-(U13-SENSOR_VN-Pad5)") (class "Default")
      (node (ref "U13") (pin "5") (pinfunction "SENSOR_VN_5") (pintype "unspecified+no_connect"))
    )
    (net (code "87") (name "unconnected-(U13-SENSOR_VP-Pad4)") (class "Default")
      (node (ref "U13") (pin "4") (pinfunction "SENSOR_VP_4") (pintype "unspecified+no_connect"))
    )
    (net (code "88") (name "unconnected-(U13-SHD{slash}SD2-Pad17)") (class "Default")
      (node (ref "U13") (pin "17") (pinfunction "SHD/SD2_17") (pintype "unspecified+no_connect"))
    )
    (net (code "89") (name "unconnected-(U13-SWP{slash}SD3-Pad18)") (class "Default")
      (node (ref "U13") (pin "18") (pinfunction "SWP/SD3_18") (pintype "unspecified+no_connect"))
    )
    (net (code "90") (name "unconnected-(U15-Vout-Pad4)") (class "Default")
      (node (ref "U15") (pin "4") (pinfunction "Vout_4") (pintype "unspecified+no_connect"))
    )
  )
)
